# TP1_NodoWiFi_Per_Rev0.net
KiCad netlist of a schematic drawn in Altium Designer
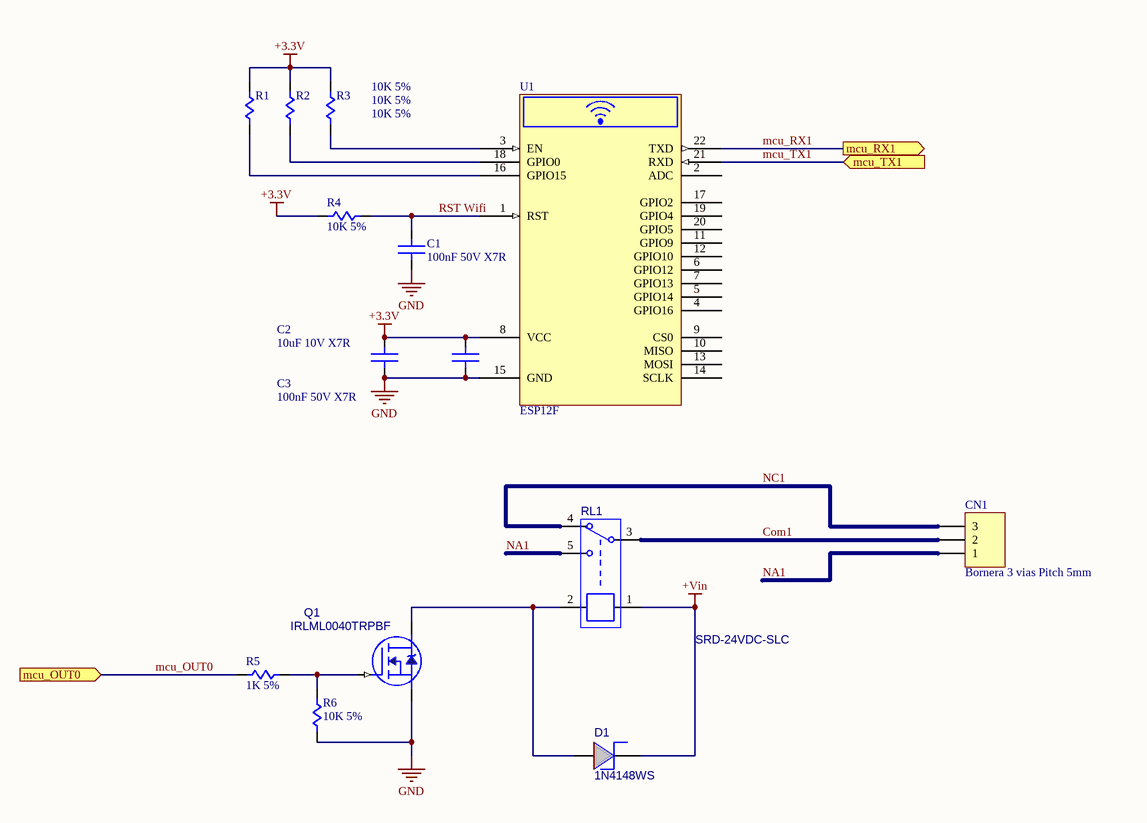
[diagram p0: TP1_NodoWiFi_Per_Rev0.SchDoc]

(export (version "E")
  (design (tool "Eeschema 10.0.6"))
  (components
    (comp (ref "C1")
      (value "100nF 50V X7R")
      (footprint "IDCI_WifiNode:C_0805")
      (description "capacitor no polarizado")
      (libsource (lib "WifiNode") (part "Capacitor_NoP"))
    )
    (comp (ref "C2")
      (value "10uF 10V X7R")
      (footprint "IDCI_WifiNode:C_0805")
      (description "capacitor no polarizado")
      (libsource (lib "WifiNode") (part "Capacitor_NoP"))
    )
    (comp (ref "C3")
      (value "100nF 50V X7R")
      (footprint "IDCI_WifiNode:C_0805")
      (description "capacitor no polarizado")
      (libsource (lib "WifiNode") (part "Capacitor_NoP"))
    )
    (comp (ref "CN1")
      (value "Bornera 3 vias Pitch 5mm")
      (footprint "TerminalBlock_1x3_P5mm")
      (description "Connector Generic 3 Vias")
      (libsource (lib "WifiNode") (part "CONN_03P"))
    )
    (comp (ref "D1")
      (value "1N4148WS")
      (footprint "IDCI_WifiNode:D_0805")
      (description "Diode Shottky")
      (libsource (lib "WifiNode") (part "DIODO_SH"))
    )
    (comp (ref "Q1")
      (value "IRLML0040TRPBF")
      (footprint "IDCI_WifiNode:SOT_23")
      (description "Mosfet N-Ch")
      (libsource (lib "WifiNode") (part "N_MOSFET_SOT23"))
    )
    (comp (ref "R1")
      (value "10K 5%")
      (footprint "IDCI_WifiNode:R_0805")
      (description "Resistor")
      (libsource (lib "WifiNode") (part "Resistencia"))
    )
    (comp (ref "R2")
      (value "10K 5%")
      (footprint "IDCI_WifiNode:R_0805")
      (description "Resistor")
      (libsource (lib "WifiNode") (part "Resistencia"))
    )
    (comp (ref "R3")
      (value "10K 5%")
      (footprint "IDCI_WifiNode:R_0805")
      (description "Resistor")
      (libsource (lib "WifiNode") (part "Resistencia"))
    )
    (comp (ref "R4")
      (value "10K 5%")
      (footprint "IDCI_WifiNode:R_0805")
      (description "Resistor")
      (libsource (lib "WifiNode") (part "Resistencia"))
    )
    (comp (ref "R5")
      (value "1K 5%")
      (footprint "IDCI_WifiNode:R_0805")
      (description "Resistor")
      (libsource (lib "WifiNode") (part "Resistencia"))
    )
    (comp (ref "R6")
      (value "10K 5%")
      (footprint "R_0805")
      (description "Resistor")
      (libsource (lib "WifiNode") (part "Resistencia"))
    )
    (comp (ref "RL1")
      (value "SRD-24VDC-SLC")
      (footprint "IDCI_WifiNode:943-1C")
      (description "Relay SPDT")
      (libsource (lib "WifiNode") (part "RELAY SPDT"))
    )
    (comp (ref "U1")
      (value "ESP12F")
      (footprint "IDCI_WifiNode:ESP12F")
      (description "Wifi Module")
      (libsource (lib "WifiNode") (part "ESP12F Wifi Module"))
    )
  )
  (nets
    (net (code "1") (name "+3.3V") (class "Default")
      (node (ref "C2") (pin "2") (pinfunction "Cap_2") (pintype "passive"))
      (node (ref "C3") (pin "2") (pinfunction "Cap_2") (pintype "passive"))
      (node (ref "R1") (pin "2") (pinfunction "Cap_2") (pintype "passive"))
      (node (ref "R2") (pin "2") (pinfunction "Cap_2") (pintype "passive"))
      (node (ref "R3") (pin "2") (pinfunction "Cap_2") (pintype "passive"))
      (node (ref "R4") (pin "2") (pinfunction "Cap_2") (pintype "passive"))
      (node (ref "U1") (pin "8") (pinfunction "VCC_8") (pintype "power_in"))
    )
    (net (code "2") (name "+Vin") (class "Default")
      (node (ref "D1") (pin "2") (pinfunction "K_2") (pintype "passive"))
      (node (ref "RL1") (pin "1") (pinfunction "1_1") (pintype "passive"))
    )
    (net (code "3") (name "/Com1") (class "Default")
      (node (ref "CN1") (pin "2") (pinfunction "2_2") (pintype "passive"))
      (node (ref "RL1") (pin "3") (pinfunction "3_3") (pintype "passive"))
    )
    (net (code "4") (name "/NA1") (class "Default")
      (node (ref "CN1") (pin "1") (pinfunction "1_1") (pintype "passive"))
      (node (ref "RL1") (pin "5") (pinfunction "5_5") (pintype "passive"))
    )
    (net (code "5") (name "/NC1") (class "Default")
      (node (ref "CN1") (pin "3") (pinfunction "3_3") (pintype "passive"))
      (node (ref "RL1") (pin "4") (pinfunction "4_4") (pintype "passive"))
    )
    (net (code "6") (name "/RST Wifi") (class "Default")
      (node (ref "C1") (pin "2") (pinfunction "Cap_2") (pintype "passive"))
      (node (ref "R4") (pin "1") (pinfunction "Cap_1") (pintype "passive"))
      (node (ref "U1") (pin "1") (pinfunction "RST_1") (pintype "input"))
    )
    (net (code "7") (name "/mcu_OUT0") (class "Default")
      (node (ref "R5") (pin "2") (pinfunction "Cap_2") (pintype "passive"))
    )
    (net (code "8") (name "/mcu_RX1") (class "Default")
      (node (ref "U1") (pin "22") (pinfunction "TXD_22") (pintype "output"))
    )
    (net (code "9") (name "/mcu_TX1") (class "Default")
      (node (ref "U1") (pin "21") (pinfunction "RXD_21") (pintype "input"))
    )
    (net (code "10") (name "GND") (class "Default")
      (node (ref "C1") (pin "1") (pinfunction "Cap_1") (pintype "passive"))
      (node (ref "C2") (pin "1") (pinfunction "Cap_1") (pintype "passive"))
      (node (ref "C3") (pin "1") (pinfunction "Cap_1") (pintype "passive"))
      (node (ref "Q1") (pin "2") (pinfunction "SOURCE_2") (pintype "passive"))
      (node (ref "R6") (pin "1") (pinfunction "Cap_1") (pintype "passive"))
      (node (ref "U1") (pin "15") (pinfunction "GND_15") (pintype "power_in"))
    )
    (net (code "11") (name "Net-(D1-A)") (class "Default")
      (node (ref "D1") (pin "1") (pinfunction "A_1") (pintype "passive"))
      (node (ref "Q1") (pin "3") (pinfunction "DRAIN_3") (pintype "passive"))
      (node (ref "RL1") (pin "2") (pinfunction "2_2") (pintype "passive"))
    )
    (net (code "12") (name "Net-(Q1-GATE)") (class "Default")
      (node (ref "Q1") (pin "1") (pinfunction "GATE_1") (pintype "input"))
      (node (ref "R5") (pin "1") (pinfunction "Cap_1") (pintype "passive"))
      (node (ref "R6") (pin "2") (pinfunction "Cap_2") (pintype "passive"))
    )
    (net (code "13") (name "Net-(U1-EN)") (class "Default")
      (node (ref "R3") (pin "1") (pinfunction "Cap_1") (pintype "passive"))
      (node (ref "U1") (pin "3") (pinfunction "EN_3") (pintype "input"))
    )
    (net (code "14") (name "Net-(U1-GPIO0)") (class "Default")
      (node (ref "R2") (pin "1") (pinfunction "Cap_1") (pintype "passive"))
      (node (ref "U1") (pin "18") (pinfunction "GPIO0_18") (pintype "passive"))
    )
    (net (code "15") (name "Net-(U1-GPIO15)") (class "Default")
      (node (ref "R1") (pin "1") (pinfunction "Cap_1") (pintype "passive"))
      (node (ref "U1") (pin "16") (pinfunction "GPIO15_16") (pintype "passive"))
    )
    (net (code "16") (name "unconnected-(U1-ADC-Pad2)") (class "Default")
      (node (ref "U1") (pin "2") (pinfunction "ADC_2") (pintype "passive"))
    )
    (net (code "17") (name "unconnected-(U1-CS0-Pad9)") (class "Default")
      (node (ref "U1") (pin "9") (pinfunction "CS0_9") (pintype "passive"))
    )
    (net (code "18") (name "unconnected-(U1-GPIO2-Pad17)") (class "Default")
      (node (ref "U1") (pin "17") (pinfunction "GPIO2_17") (pintype "passive"))
    )
    (net (code "19") (name "unconnected-(U1-GPIO4-Pad19)") (class "Default")
      (node (ref "U1") (pin "19") (pinfunction "GPIO4_19") (pintype "passive"))
    )
    (net (code "20") (name "unconnected-(U1-GPIO5-Pad20)") (class "Default")
      (node (ref "U1") (pin "20") (pinfunction "GPIO5_20") (pintype "passive"))
    )
    (net (code "21") (name "unconnected-(U1-GPIO9-Pad11)") (class "Default")
      (node (ref "U1") (pin "11") (pinfunction "GPIO9_11") (pintype "passive"))
    )
    (net (code "22") (name "unconnected-(U1-GPIO10-Pad12)") (class "Default")
      (node (ref "U1") (pin "12") (pinfunction "GPIO10_12") (pintype "passive"))
    )
    (net (code "23") (name "unconnected-(U1-GPIO12-Pad6)") (class "Default")
      (node (ref "U1") (pin "6") (pinfunction "GPIO12_6") (pintype "passive"))
    )
    (net (code "24") (name "unconnected-(U1-GPIO13-Pad7)") (class "Default")
      (node (ref "U1") (pin "7") (pinfunction "GPIO13_7") (pintype "passive"))
    )
    (net (code "25") (name "unconnected-(U1-GPIO14-Pad5)") (class "Default")
      (node (ref "U1") (pin "5") (pinfunction "GPIO14_5") (pintype "passive"))
    )
    (net (code "26") (name "unconnected-(U1-GPIO16-Pad4)") (class "Default")
      (node (ref "U1") (pin "4") (pinfunction "GPIO16_4") (pintype "passive"))
    )
    (net (code "27") (name "unconnected-(U1-MISO-Pad10)") (class "Default")
      (node (ref "U1") (pin "10") (pinfunction "MISO_10") (pintype "passive"))
    )
    (net (code "28") (name "unconnected-(U1-MOSI-Pad13)") (class "Default")
      (node (ref "U1") (pin "13") (pinfunction "MOSI_13") (pintype "passive"))
    )
    (net (code "29") (name "unconnected-(U1-SCLK-Pad14)") (class "Default")
      (node (ref "U1") (pin "14") (pinfunction "SCLK_14") (pintype "passive"))
    )
  )
)
